# Connector_0.net
KiCad netlist of a schematic drawn in Altium Designer
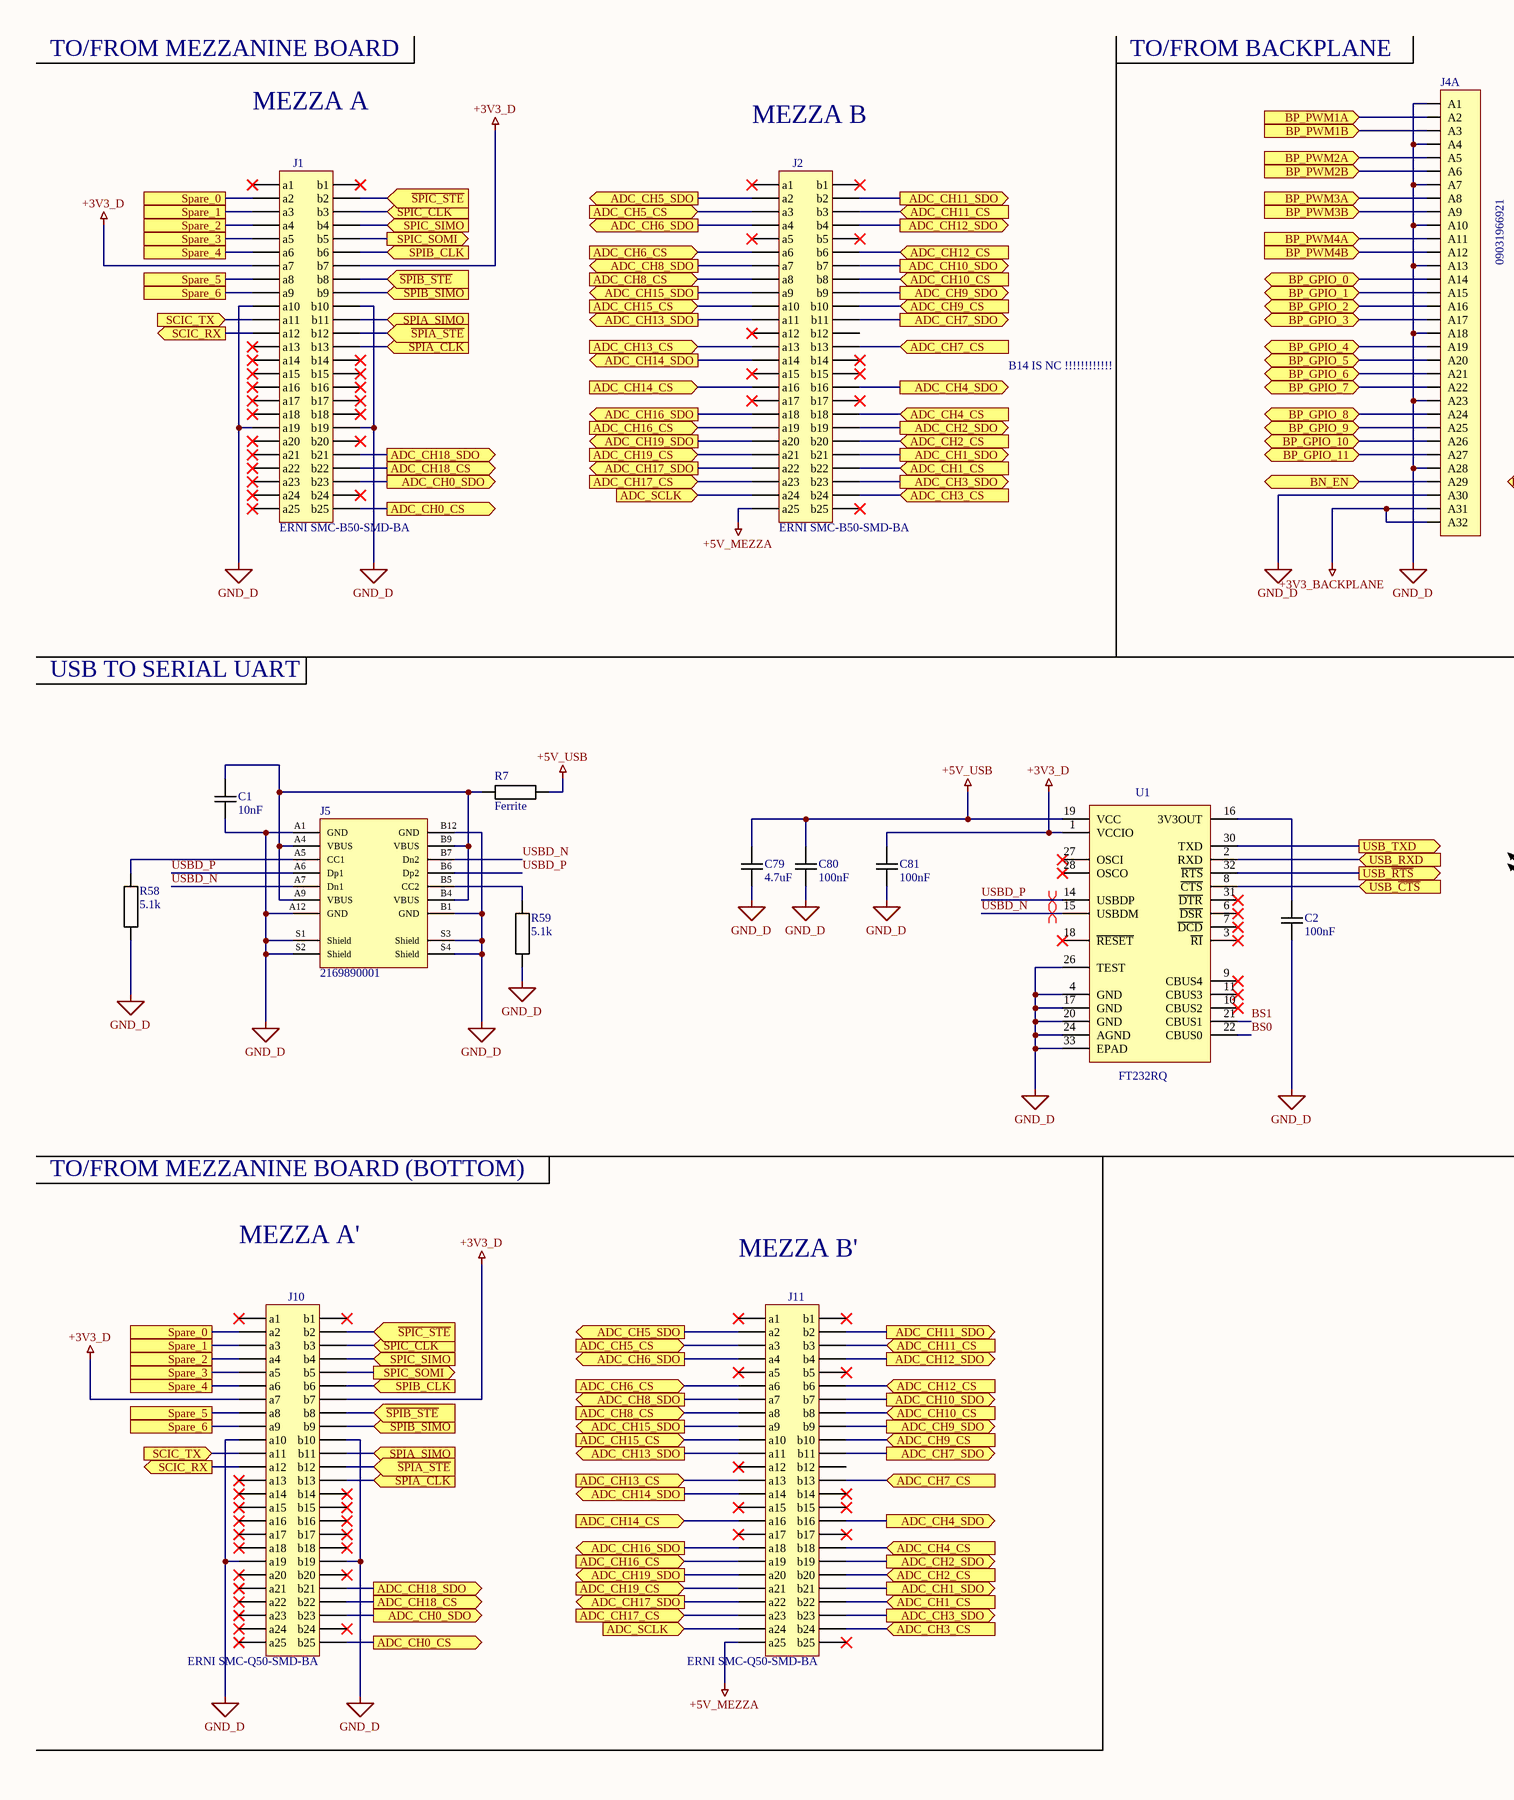
[diagram p0: Connector_0.SchDoc, left]
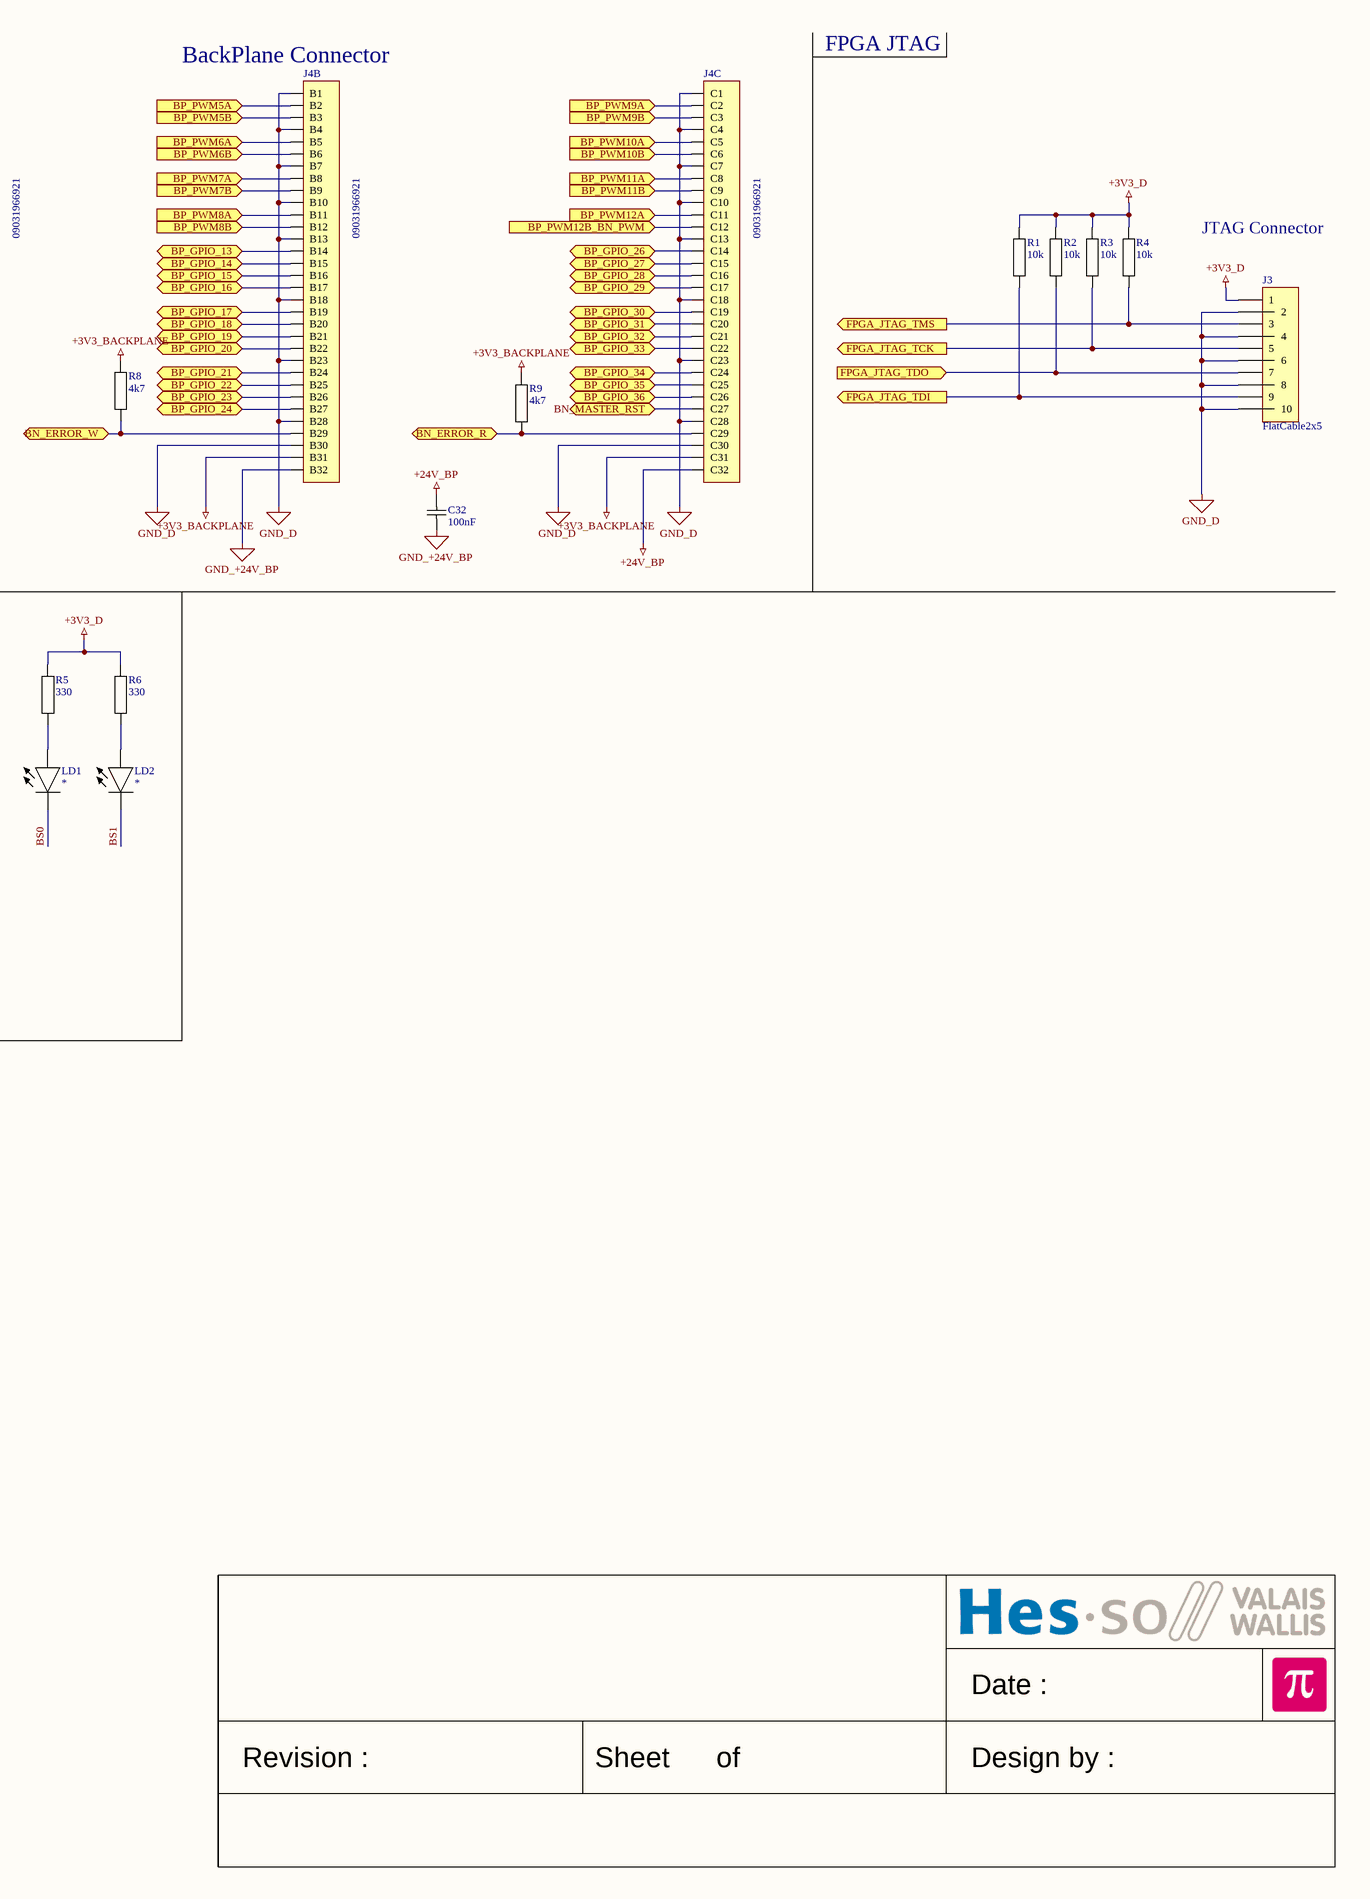
[diagram p1: Connector_0.SchDoc, right]

(export (version "E")
  (design (tool "Eeschema 10.0.6"))
  (components
    (comp (ref "C1")
      (value "10nF")
      (footprint "CAPACITOR 1608 REFLOW")
      (description "Capacitor X7R 10% 50V 1608(0603)")
      (libsource (lib "Capacitor") (part "Capacitor"))
    )
    (comp (ref "C2")
      (value "100nF")
      (footprint "CAPACITOR 1608 REFLOW")
      (description "Capacitor X7R 10% 50V 1608(0603)")
      (libsource (lib "Capacitor") (part "Capacitor"))
    )
    (comp (ref "C32")
      (value "100nF")
      (footprint "CAPACITOR 1608 REFLOW")
      (description "Capacitor X7R 10% 50V 1608(0603)")
      (libsource (lib "Capacitor") (part "Capacitor"))
    )
    (comp (ref "C79")
      (value "4.7uF")
      (footprint "CAPACITOR 1608 REFLOW")
      (description "Capacitor X7R 10% 50V 1608(0603)")
      (libsource (lib "Capacitor") (part "Capacitor"))
    )
    (comp (ref "C80")
      (value "100nF")
      (footprint "CAPACITOR 1608 REFLOW")
      (description "Capacitor X7R 10% 50V 1608(0603)")
      (libsource (lib "Capacitor") (part "Capacitor"))
    )
    (comp (ref "C81")
      (value "100nF")
      (footprint "CAPACITOR 1608 REFLOW")
      (description "Capacitor X7R 10% 50V 1608(0603)")
      (libsource (lib "Capacitor") (part "Capacitor"))
    )
    (comp (ref "J1")
      (value "ERNI SMC-B50-SMD-BA")
      (footprint "ERNI SMC-B50-SMD-BA")
      (description "Female 1.27 pitch 2x25 pin connector")
      (libsource (lib "Connector") (part "ERNI SMC-B50-SMD-BA"))
    )
    (comp (ref "J2")
      (value "ERNI SMC-B50-SMD-BA")
      (footprint "ERNI SMC-B50-SMD-BA")
      (description "Female 1.27 pitch 2x25 pin connector")
      (libsource (lib "Connector") (part "ERNI SMC-B50-SMD-BA"))
    )
    (comp (ref "J3")
      (value "FlatCable2x5")
      (footprint "FlatCable2x5 2MM Right Angle TH FCI 98614-G61-10ULF")
      (libsource (lib "Connector") (part "FlatCable2x5"))
    )
    (comp (ref "J4")
      (value "09031966921")
      (footprint "DIN41612 MALE 3X32 ABC R90")
      (description "DIN41612 MALE 3X32 ABC R90")
      (fields (field (name "MANUFACTURER") "Harting"))
      (libsource (lib "Connector") (part "DIN41612 MALE 3X32 ABC R90"))
    )
    (comp (ref "J5")
      (value "2169890001")
      (footprint "USB-C-TH MOLEX 2169890001")
      (description "USB-C Receptacle Connector 24 Position Through Hole, Right Angle")
      (libsource (lib "Connector") (part "USB-C-Molex 2169890001"))
    )
    (comp (ref "J10")
      (value "ERNI SMC-Q50-SMD-BA")
      (footprint "ERNI SMC-Q50-SMD-BA")
      (description "Male 1.27 pitch 2x25 pin connector")
      (libsource (lib "Connector") (part "ERNI SMC-Q50-SMD-BA"))
    )
    (comp (ref "J11")
      (value "ERNI SMC-Q50-SMD-BA")
      (footprint "ERNI SMC-Q50-SMD-BA")
      (description "Male 1.27 pitch 2x25 pin connector")
      (libsource (lib "Connector") (part "ERNI SMC-Q50-SMD-BA"))
    )
    (comp (ref "LD1")
      (value "*")
      (footprint "LED 1608 REFLOW")
      (description "LED generic")
      (libsource (lib "Diode") (part "LED"))
    )
    (comp (ref "LD2")
      (value "*")
      (footprint "LED 1608 REFLOW")
      (description "LED generic")
      (libsource (lib "Diode") (part "LED"))
    )
    (comp (ref "R1")
      (value "10k")
      (footprint "RESISTOR 1608 REFLOW")
      (description "Resistor 1% 50V 100mW 1608(0603)")
      (libsource (lib "Resistor") (part "Resistor"))
    )
    (comp (ref "R2")
      (value "10k")
      (footprint "RESISTOR 1608 REFLOW")
      (description "Resistor 1% 50V 100mW 1608(0603)")
      (libsource (lib "Resistor") (part "Resistor"))
    )
    (comp (ref "R3")
      (value "10k")
      (footprint "RESISTOR 1608 REFLOW")
      (description "Resistor 1% 50V 100mW 1608(0603)")
      (libsource (lib "Resistor") (part "Resistor"))
    )
    (comp (ref "R4")
      (value "10k")
      (footprint "RESISTOR 1608 REFLOW")
      (description "Resistor 1% 50V 100mW 1608(0603)")
      (libsource (lib "Resistor") (part "Resistor"))
    )
    (comp (ref "R5")
      (value "330")
      (footprint "RESISTOR 1608 REFLOW")
      (description "Resistor 1% 50V 125mW 2012(0805)")
      (libsource (lib "Resistor") (part "Resistor"))
    )
    (comp (ref "R6")
      (value "330")
      (footprint "RESISTOR 1608 REFLOW")
      (description "Resistor 1% 50V 125mW 2012(0805)")
      (libsource (lib "Resistor") (part "Resistor"))
    )
    (comp (ref "R7")
      (value "Ferrite")
      (footprint "RESISTOR 1608 REFLOW")
      (description "Resistor 1% 50V 100mW 1608(0603)")
      (libsource (lib "Resistor") (part "Resistor"))
    )
    (comp (ref "R8")
      (value "4k7")
      (footprint "RESISTOR 1608 REFLOW")
      (description "Resistor 1% 50V 100mW 1608(0603)")
      (libsource (lib "Resistor") (part "Resistor"))
    )
    (comp (ref "R9")
      (value "4k7")
      (footprint "RESISTOR 1608 REFLOW")
      (description "Resistor 1% 50V 100mW 1608(0603)")
      (libsource (lib "Resistor") (part "Resistor"))
    )
    (comp (ref "R58")
      (value "5.1k")
      (footprint "RESISTOR 1608 REFLOW")
      (description "Resistor 1% 50V 100mW 1608(0603)")
      (libsource (lib "Resistor") (part "Resistor"))
    )
    (comp (ref "R59")
      (value "5.1k")
      (footprint "RESISTOR 1608 REFLOW")
      (description "Resistor 1% 50V 100mW 1608(0603)")
      (libsource (lib "Resistor") (part "Resistor"))
    )
    (comp (ref "U1")
      (value "FT232RQ")
      (footprint "QFN32 P0.5 T3.2x3.2 C5.0X5.0 H1.0")
      (description "24-Bit ADC with Ultra Low Noise PGIA - Crystal")
      (libsource (lib "IntegratedCircuit - Copy") (part "FT232RQ"))
    )
  )
  (nets
    (net (code "1") (name "+3V3_BACKPLANE") (class "Default")
      (node (ref "J4") (pin "A31") (pinfunction "A31_A31") (pintype "passive"))
      (node (ref "J4") (pin "A32") (pinfunction "A32_A32") (pintype "passive"))
      (node (ref "J4") (pin "B31") (pinfunction "B31_B31") (pintype "passive"))
      (node (ref "J4") (pin "C31") (pinfunction "C31_C31") (pintype "passive"))
      (node (ref "R8") (pin "2") (pinfunction "2_2") (pintype "passive"))
      (node (ref "R9") (pin "2") (pinfunction "2_2") (pintype "passive"))
    )
    (net (code "2") (name "+3V3_D") (class "Default")
      (node (ref "C81") (pin "2") (pinfunction "2_2") (pintype "passive"))
      (node (ref "J1") (pin "a7") (pinfunction "a7_a7") (pintype "passive"))
      (node (ref "J1") (pin "b7") (pinfunction "b7_b7") (pintype "passive"))
      (node (ref "J10") (pin "a7") (pinfunction "a7_a7") (pintype "passive"))
      (node (ref "J10") (pin "b7") (pinfunction "b7_b7") (pintype "passive"))
      (node (ref "J3") (pin "1") (pinfunction "1_1") (pintype "passive"))
      (node (ref "R1") (pin "2") (pinfunction "2_2") (pintype "passive"))
      (node (ref "R2") (pin "2") (pinfunction "2_2") (pintype "passive"))
      (node (ref "R3") (pin "2") (pinfunction "2_2") (pintype "passive"))
      (node (ref "R4") (pin "2") (pinfunction "2_2") (pintype "passive"))
      (node (ref "R5") (pin "2") (pinfunction "2_2") (pintype "passive"))
      (node (ref "R6") (pin "2") (pinfunction "2_2") (pintype "passive"))
      (node (ref "U1") (pin "1") (pinfunction "VCCIO_1") (pintype "passive"))
    )
    (net (code "3") (name "+5V_MEZZA") (class "Default")
      (node (ref "J11") (pin "a25") (pinfunction "a25_a25") (pintype "passive"))
      (node (ref "J2") (pin "a25") (pinfunction "a25_a25") (pintype "passive"))
    )
    (net (code "4") (name "+5V_USB") (class "Default")
      (node (ref "C79") (pin "2") (pinfunction "2_2") (pintype "passive"))
      (node (ref "C80") (pin "2") (pinfunction "2_2") (pintype "passive"))
      (node (ref "R7") (pin "2") (pinfunction "2_2") (pintype "passive"))
      (node (ref "U1") (pin "19") (pinfunction "VCC_19") (pintype "passive"))
    )
    (net (code "5") (name "+24V_BP") (class "Default")
      (node (ref "C32") (pin "2") (pinfunction "2_2") (pintype "passive"))
      (node (ref "J4") (pin "C32") (pinfunction "C32_C32") (pintype "passive"))
    )
    (net (code "6") (name "/ADC_CH0_CS") (class "Default")
      (node (ref "J1") (pin "b25") (pinfunction "b25_b25") (pintype "passive"))
      (node (ref "J10") (pin "b25") (pinfunction "b25_b25") (pintype "passive"))
    )
    (net (code "7") (name "/ADC_CH0_SDO") (class "Default")
      (node (ref "J1") (pin "b23") (pinfunction "b23_b23") (pintype "passive"))
      (node (ref "J10") (pin "b23") (pinfunction "b23_b23") (pintype "passive"))
    )
    (net (code "8") (name "/ADC_CH1_CS") (class "Default")
      (node (ref "J11") (pin "b22") (pinfunction "b22_b22") (pintype "passive"))
      (node (ref "J2") (pin "b22") (pinfunction "b22_b22") (pintype "passive"))
    )
    (net (code "9") (name "/ADC_CH1_SDO") (class "Default")
      (node (ref "J11") (pin "b21") (pinfunction "b21_b21") (pintype "passive"))
      (node (ref "J2") (pin "b21") (pinfunction "b21_b21") (pintype "passive"))
    )
    (net (code "10") (name "/ADC_CH2_CS") (class "Default")
      (node (ref "J11") (pin "b20") (pinfunction "b20_b20") (pintype "passive"))
      (node (ref "J2") (pin "b20") (pinfunction "b20_b20") (pintype "passive"))
    )
    (net (code "11") (name "/ADC_CH2_SDO") (class "Default")
      (node (ref "J11") (pin "b19") (pinfunction "b19_b19") (pintype "passive"))
      (node (ref "J2") (pin "b19") (pinfunction "b19_b19") (pintype "passive"))
    )
    (net (code "12") (name "/ADC_CH3_CS") (class "Default")
      (node (ref "J11") (pin "b24") (pinfunction "b24_b24") (pintype "passive"))
      (node (ref "J2") (pin "b24") (pinfunction "b24_b24") (pintype "passive"))
    )
    (net (code "13") (name "/ADC_CH3_SDO") (class "Default")
      (node (ref "J11") (pin "b23") (pinfunction "b23_b23") (pintype "passive"))
      (node (ref "J2") (pin "b23") (pinfunction "b23_b23") (pintype "passive"))
    )
    (net (code "14") (name "/ADC_CH4_CS") (class "Default")
      (node (ref "J11") (pin "b18") (pinfunction "b18_b18") (pintype "passive"))
      (node (ref "J2") (pin "b18") (pinfunction "b18_b18") (pintype "passive"))
    )
    (net (code "15") (name "/ADC_CH4_SDO") (class "Default")
      (node (ref "J11") (pin "b16") (pinfunction "b16_b16") (pintype "passive"))
      (node (ref "J2") (pin "b16") (pinfunction "b16_b16") (pintype "passive"))
    )
    (net (code "16") (name "/ADC_CH5_CS") (class "Default")
      (node (ref "J11") (pin "a3") (pinfunction "a3_a3") (pintype "passive"))
      (node (ref "J2") (pin "a3") (pinfunction "a3_a3") (pintype "passive"))
    )
    (net (code "17") (name "/ADC_CH5_SDO") (class "Default")
      (node (ref "J11") (pin "a2") (pinfunction "a2_a2") (pintype "passive"))
      (node (ref "J2") (pin "a2") (pinfunction "a2_a2") (pintype "passive"))
    )
    (net (code "18") (name "/ADC_CH6_CS") (class "Default")
      (node (ref "J11") (pin "a6") (pinfunction "a6_a6") (pintype "passive"))
      (node (ref "J2") (pin "a6") (pinfunction "a6_a6") (pintype "passive"))
    )
    (net (code "19") (name "/ADC_CH6_SDO") (class "Default")
      (node (ref "J11") (pin "a4") (pinfunction "a4_a4") (pintype "passive"))
      (node (ref "J2") (pin "a4") (pinfunction "a4_a4") (pintype "passive"))
    )
    (net (code "20") (name "/ADC_CH7_CS") (class "Default")
      (node (ref "J11") (pin "b13") (pinfunction "b13_b13") (pintype "passive"))
      (node (ref "J2") (pin "b13") (pinfunction "b13_b13") (pintype "passive"))
    )
    (net (code "21") (name "/ADC_CH7_SDO") (class "Default")
      (node (ref "J11") (pin "b11") (pinfunction "b11_b11") (pintype "passive"))
      (node (ref "J2") (pin "b11") (pinfunction "b11_b11") (pintype "passive"))
    )
    (net (code "22") (name "/ADC_CH8_CS") (class "Default")
      (node (ref "J11") (pin "a8") (pinfunction "a8_a8") (pintype "passive"))
      (node (ref "J2") (pin "a8") (pinfunction "a8_a8") (pintype "passive"))
    )
    (net (code "23") (name "/ADC_CH8_SDO") (class "Default")
      (node (ref "J11") (pin "a7") (pinfunction "a7_a7") (pintype "passive"))
      (node (ref "J2") (pin "a7") (pinfunction "a7_a7") (pintype "passive"))
    )
    (net (code "24") (name "/ADC_CH9_CS") (class "Default")
      (node (ref "J11") (pin "b10") (pinfunction "b10_b10") (pintype "passive"))
      (node (ref "J2") (pin "b10") (pinfunction "b10_b10") (pintype "passive"))
    )
    (net (code "25") (name "/ADC_CH9_SDO") (class "Default")
      (node (ref "J11") (pin "b9") (pinfunction "b9_b9") (pintype "passive"))
      (node (ref "J2") (pin "b9") (pinfunction "b9_b9") (pintype "passive"))
    )
    (net (code "26") (name "/ADC_CH10_CS") (class "Default")
      (node (ref "J11") (pin "b8") (pinfunction "b8_b8") (pintype "passive"))
      (node (ref "J2") (pin "b8") (pinfunction "b8_b8") (pintype "passive"))
    )
    (net (code "27") (name "/ADC_CH10_SDO") (class "Default")
      (node (ref "J11") (pin "b7") (pinfunction "b7_b7") (pintype "passive"))
      (node (ref "J2") (pin "b7") (pinfunction "b7_b7") (pintype "passive"))
    )
    (net (code "28") (name "/ADC_CH11_CS") (class "Default")
      (node (ref "J11") (pin "b3") (pinfunction "b3_b3") (pintype "passive"))
      (node (ref "J2") (pin "b3") (pinfunction "b3_b3") (pintype "passive"))
    )
    (net (code "29") (name "/ADC_CH11_SDO") (class "Default")
      (node (ref "J11") (pin "b2") (pinfunction "b2_b2") (pintype "passive"))
      (node (ref "J2") (pin "b2") (pinfunction "b2_b2") (pintype "passive"))
    )
    (net (code "30") (name "/ADC_CH12_CS") (class "Default")
      (node (ref "J11") (pin "b6") (pinfunction "b6_b6") (pintype "passive"))
      (node (ref "J2") (pin "b6") (pinfunction "b6_b6") (pintype "passive"))
    )
    (net (code "31") (name "/ADC_CH12_SDO") (class "Default")
      (node (ref "J11") (pin "b4") (pinfunction "b4_b4") (pintype "passive"))
      (node (ref "J2") (pin "b4") (pinfunction "b4_b4") (pintype "passive"))
    )
    (net (code "32") (name "/ADC_CH13_CS") (class "Default")
      (node (ref "J11") (pin "a13") (pinfunction "a13_a13") (pintype "passive"))
      (node (ref "J2") (pin "a13") (pinfunction "a13_a13") (pintype "passive"))
    )
    (net (code "33") (name "/ADC_CH13_SDO") (class "Default")
      (node (ref "J11") (pin "a11") (pinfunction "a11_a11") (pintype "passive"))
      (node (ref "J2") (pin "a11") (pinfunction "a11_a11") (pintype "passive"))
    )
    (net (code "34") (name "/ADC_CH14_CS") (class "Default")
      (node (ref "J11") (pin "a16") (pinfunction "a16_a16") (pintype "passive"))
      (node (ref "J2") (pin "a16") (pinfunction "a16_a16") (pintype "passive"))
    )
    (net (code "35") (name "/ADC_CH14_SDO") (class "Default")
      (node (ref "J11") (pin "a14") (pinfunction "a14_a14") (pintype "passive"))
      (node (ref "J2") (pin "a14") (pinfunction "a14_a14") (pintype "passive"))
    )
    (net (code "36") (name "/ADC_CH15_CS") (class "Default")
      (node (ref "J11") (pin "a10") (pinfunction "a10_a10") (pintype "passive"))
      (node (ref "J2") (pin "a10") (pinfunction "a10_a10") (pintype "passive"))
    )
    (net (code "37") (name "/ADC_CH15_SDO") (class "Default")
      (node (ref "J11") (pin "a9") (pinfunction "a9_a9") (pintype "passive"))
      (node (ref "J2") (pin "a9") (pinfunction "a9_a9") (pintype "passive"))
    )
    (net (code "38") (name "/ADC_CH16_CS") (class "Default")
      (node (ref "J11") (pin "a19") (pinfunction "a19_a19") (pintype "passive"))
      (node (ref "J2") (pin "a19") (pinfunction "a19_a19") (pintype "passive"))
    )
    (net (code "39") (name "/ADC_CH16_SDO") (class "Default")
      (node (ref "J11") (pin "a18") (pinfunction "a18_a18") (pintype "passive"))
      (node (ref "J2") (pin "a18") (pinfunction "a18_a18") (pintype "passive"))
    )
    (net (code "40") (name "/ADC_CH17_CS") (class "Default")
      (node (ref "J11") (pin "a23") (pinfunction "a23_a23") (pintype "passive"))
      (node (ref "J2") (pin "a23") (pinfunction "a23_a23") (pintype "passive"))
    )
    (net (code "41") (name "/ADC_CH17_SDO") (class "Default")
      (node (ref "J11") (pin "a22") (pinfunction "a22_a22") (pintype "passive"))
      (node (ref "J2") (pin "a22") (pinfunction "a22_a22") (pintype "passive"))
    )
    (net (code "42") (name "/ADC_CH18_CS") (class "Default")
      (node (ref "J1") (pin "b22") (pinfunction "b22_b22") (pintype "passive"))
      (node (ref "J10") (pin "b22") (pinfunction "b22_b22") (pintype "passive"))
    )
    (net (code "43") (name "/ADC_CH18_SDO") (class "Default")
      (node (ref "J1") (pin "b21") (pinfunction "b21_b21") (pintype "passive"))
      (node (ref "J10") (pin "b21") (pinfunction "b21_b21") (pintype "passive"))
    )
    (net (code "44") (name "/ADC_CH19_CS") (class "Default")
      (node (ref "J11") (pin "a21") (pinfunction "a21_a21") (pintype "passive"))
      (node (ref "J2") (pin "a21") (pinfunction "a21_a21") (pintype "passive"))
    )
    (net (code "45") (name "/ADC_CH19_SDO") (class "Default")
      (node (ref "J11") (pin "a20") (pinfunction "a20_a20") (pintype "passive"))
      (node (ref "J2") (pin "a20") (pinfunction "a20_a20") (pintype "passive"))
    )
    (net (code "46") (name "/ADC_SCLK") (class "Default")
      (node (ref "J11") (pin "a24") (pinfunction "a24_a24") (pintype "passive"))
      (node (ref "J2") (pin "a24") (pinfunction "a24_a24") (pintype "passive"))
    )
    (net (code "47") (name "/BN_EN") (class "Default")
      (node (ref "J4") (pin "A29") (pinfunction "A29_A29") (pintype "passive"))
    )
    (net (code "48") (name "/BN_ERROR_R") (class "Default")
      (node (ref "J4") (pin "C29") (pinfunction "C29_C29") (pintype "passive"))
      (node (ref "R9") (pin "1") (pinfunction "1_1") (pintype "passive"))
    )
    (net (code "49") (name "/BN_ERROR_W") (class "Default")
      (node (ref "J4") (pin "B29") (pinfunction "B29_B29") (pintype "passive"))
      (node (ref "R8") (pin "1") (pinfunction "1_1") (pintype "passive"))
    )
    (net (code "50") (name "/BN_MASTER_RST") (class "Default")
      (node (ref "J4") (pin "C27") (pinfunction "C27_C27") (pintype "passive"))
    )
    (net (code "51") (name "/BP_GPIO_0") (class "Default")
      (node (ref "J4") (pin "A14") (pinfunction "A14_A14") (pintype "passive"))
    )
    (net (code "52") (name "/BP_GPIO_1") (class "Default")
      (node (ref "J4") (pin "A15") (pinfunction "A15_A15") (pintype "passive"))
    )
    (net (code "53") (name "/BP_GPIO_2") (class "Default")
      (node (ref "J4") (pin "A16") (pinfunction "A16_A16") (pintype "passive"))
    )
    (net (code "54") (name "/BP_GPIO_3") (class "Default")
      (node (ref "J4") (pin "A17") (pinfunction "A17_A17") (pintype "passive"))
    )
    (net (code "55") (name "/BP_GPIO_4") (class "Default")
      (node (ref "J4") (pin "A19") (pinfunction "A19_A19") (pintype "passive"))
    )
    (net (code "56") (name "/BP_GPIO_5") (class "Default")
      (node (ref "J4") (pin "A20") (pinfunction "A20_A20") (pintype "passive"))
    )
    (net (code "57") (name "/BP_GPIO_6") (class "Default")
      (node (ref "J4") (pin "A21") (pinfunction "A21_A21") (pintype "passive"))
    )
    (net (code "58") (name "/BP_GPIO_7") (class "Default")
      (node (ref "J4") (pin "A22") (pinfunction "A22_A22") (pintype "passive"))
    )
    (net (code "59") (name "/BP_GPIO_8") (class "Default")
      (node (ref "J4") (pin "A24") (pinfunction "A24_A24") (pintype "passive"))
    )
    (net (code "60") (name "/BP_GPIO_9") (class "Default")
      (node (ref "J4") (pin "A25") (pinfunction "A25_A25") (pintype "passive"))
    )
    (net (code "61") (name "/BP_GPIO_10") (class "Default")
      (node (ref "J4") (pin "A26") (pinfunction "A26_A26") (pintype "passive"))
    )
    (net (code "62") (name "/BP_GPIO_11") (class "Default")
      (node (ref "J4") (pin "A27") (pinfunction "A27_A27") (pintype "passive"))
    )
    (net (code "63") (name "/BP_GPIO_13") (class "Default")
      (node (ref "J4") (pin "B14") (pinfunction "B14_B14") (pintype "passive"))
    )
    (net (code "64") (name "/BP_GPIO_14") (class "Default")
      (node (ref "J4") (pin "B15") (pinfunction "B15_B15") (pintype "passive"))
    )
    (net (code "65") (name "/BP_GPIO_15") (class "Default")
      (node (ref "J4") (pin "B16") (pinfunction "B16_B16") (pintype "passive"))
    )
    (net (code "66") (name "/BP_GPIO_16") (class "Default")
      (node (ref "J4") (pin "B17") (pinfunction "B17_B17") (pintype "passive"))
    )
    (net (code "67") (name "/BP_GPIO_17") (class "Default")
      (node (ref "J4") (pin "B19") (pinfunction "B19_B19") (pintype "passive"))
    )
    (net (code "68") (name "/BP_GPIO_18") (class "Default")
      (node (ref "J4") (pin "B20") (pinfunction "B20_B20") (pintype "passive"))
    )
    (net (code "69") (name "/BP_GPIO_19") (class "Default")
      (node (ref "J4") (pin "B21") (pinfunction "B21_B21") (pintype "passive"))
    )
    (net (code "70") (name "/BP_GPIO_20") (class "Default")
      (node (ref "J4") (pin "B22") (pinfunction "B22_B22") (pintype "passive"))
    )
    (net (code "71") (name "/BP_GPIO_21") (class "Default")
      (node (ref "J4") (pin "B24") (pinfunction "B24_B24") (pintype "passive"))
    )
    (net (code "72") (name "/BP_GPIO_22") (class "Default")
      (node (ref "J4") (pin "B25") (pinfunction "B25_B25") (pintype "passive"))
    )
    (net (code "73") (name "/BP_GPIO_23") (class "Default")
      (node (ref "J4") (pin "B26") (pinfunction "B26_B26") (pintype "passive"))
    )
    (net (code "74") (name "/BP_GPIO_24") (class "Default")
      (node (ref "J4") (pin "B27") (pinfunction "B27_B27") (pintype "passive"))
    )
    (net (code "75") (name "/BP_GPIO_26") (class "Default")
      (node (ref "J4") (pin "C14") (pinfunction "C14_C14") (pintype "passive"))
    )
    (net (code "76") (name "/BP_GPIO_27") (class "Default")
      (node (ref "J4") (pin "C15") (pinfunction "C15_C15") (pintype "passive"))
    )
    (net (code "77") (name "/BP_GPIO_28") (class "Default")
      (node (ref "J4") (pin "C16") (pinfunction "C16_C16") (pintype "passive"))
    )
    (net (code "78") (name "/BP_GPIO_29") (class "Default")
      (node (ref "J4") (pin "C17") (pinfunction "C17_C17") (pintype "passive"))
    )
    (net (code "79") (name "/BP_GPIO_30") (class "Default")
      (node (ref "J4") (pin "C19") (pinfunction "C19_C19") (pintype "passive"))
    )
    (net (code "80") (name "/BP_GPIO_31") (class "Default")
      (node (ref "J4") (pin "C20") (pinfunction "C20_C20") (pintype "passive"))
    )
    (net (code "81") (name "/BP_GPIO_32") (class "Default")
      (node (ref "J4") (pin "C21") (pinfunction "C21_C21") (pintype "passive"))
    )
    (net (code "82") (name "/BP_GPIO_33") (class "Default")
      (node (ref "J4") (pin "C22") (pinfunction "C22_C22") (pintype "passive"))
    )
    (net (code "83") (name "/BP_GPIO_34") (class "Default")
      (node (ref "J4") (pin "C24") (pinfunction "C24_C24") (pintype "passive"))
    )
    (net (code "84") (name "/BP_GPIO_35") (class "Default")
      (node (ref "J4") (pin "C25") (pinfunction "C25_C25") (pintype "passive"))
    )
    (net (code "85") (name "/BP_GPIO_36") (class "Default")
      (node (ref "J4") (pin "C26") (pinfunction "C26_C26") (pintype "passive"))
    )
    (net (code "86") (name "/BP_PWM1A") (class "Default")
      (node (ref "J4") (pin "A2") (pinfunction "A2_A2") (pintype "passive"))
    )
    (net (code "87") (name "/BP_PWM1B") (class "Default")
      (node (ref "J4") (pin "A3") (pinfunction "A3_A3") (pintype "passive"))
    )
    (net (code "88") (name "/BP_PWM2A") (class "Default")
      (node (ref "J4") (pin "A5") (pinfunction "A5_A5") (pintype "passive"))
    )
    (net (code "89") (name "/BP_PWM2B") (class "Default")
      (node (ref "J4") (pin "A6") (pinfunction "A6_A6") (pintype "passive"))
    )
    (net (code "90") (name "/BP_PWM3A") (class "Default")
      (node (ref "J4") (pin "A8") (pinfunction "A8_A8") (pintype "passive"))
    )
    (net (code "91") (name "/BP_PWM3B") (class "Default")
      (node (ref "J4") (pin "A9") (pinfunction "A9_A9") (pintype "passive"))
    )
    (net (code "92") (name "/BP_PWM4A") (class "Default")
      (node (ref "J4") (pin "A11") (pinfunction "A11_A11") (pintype "passive"))
    )
    (net (code "93") (name "/BP_PWM4B") (class "Default")
      (node (ref "J4") (pin "A12") (pinfunction "A12_A12") (pintype "passive"))
    )
    (net (code "94") (name "/BP_PWM5A") (class "Default")
      (node (ref "J4") (pin "B2") (pinfunction "B2_B2") (pintype "passive"))
    )
    (net (code "95") (name "/BP_PWM5B") (class "Default")
      (node (ref "J4") (pin "B3") (pinfunction "B3_B3") (pintype "passive"))
    )
    (net (code "96") (name "/BP_PWM6A") (class "Default")
      (node (ref "J4") (pin "B5") (pinfunction "B5_B5") (pintype "passive"))
    )
    (net (code "97") (name "/BP_PWM6B") (class "Default")
      (node (ref "J4") (pin "B6") (pinfunction "B6_B6") (pintype "passive"))
    )
    (net (code "98") (name "/BP_PWM7A") (class "Default")
      (node (ref "J4") (pin "B8") (pinfunction "B8_B8") (pintype "passive"))
    )
    (net (code "99") (name "/BP_PWM7B") (class "Default")
      (node (ref "J4") (pin "B9") (pinfunction "B9_B9") (pintype "passive"))
    )
    (net (code "100") (name "/BP_PWM8A") (class "Default")
      (node (ref "J4") (pin "B11") (pinfunction "B11_B11") (pintype "passive"))
    )
    (net (code "101") (name "/BP_PWM8B") (class "Default")
      (node (ref "J4") (pin "B12") (pinfunction "B12_B12") (pintype "passive"))
    )
    (net (code "102") (name "/BP_PWM9A") (class "Default")
      (node (ref "J4") (pin "C2") (pinfunction "C2_C2") (pintype "passive"))
    )
    (net (code "103") (name "/BP_PWM9B") (class "Default")
      (node (ref "J4") (pin "C3") (pinfunction "C3_C3") (pintype "passive"))
    )
    (net (code "104") (name "/BP_PWM10A") (class "Default")
      (node (ref "J4") (pin "C5") (pinfunction "C5_C5") (pintype "passive"))
    )
    (net (code "105") (name "/BP_PWM10B") (class "Default")
      (node (ref "J4") (pin "C6") (pinfunction "C6_C6") (pintype "passive"))
    )
    (net (code "106") (name "/BP_PWM11A") (class "Default")
      (node (ref "J4") (pin "C8") (pinfunction "C8_C8") (pintype "passive"))
    )
    (net (code "107") (name "/BP_PWM11B") (class "Default")
      (node (ref "J4") (pin "C9") (pinfunction "C9_C9") (pintype "passive"))
    )
    (net (code "108") (name "/BP_PWM12A") (class "Default")
      (node (ref "J4") (pin "C11") (pinfunction "C11_C11") (pintype "passive"))
    )
    (net (code "109") (name "/BP_PWM12B_BN_PWM") (class "Default")
      (node (ref "J4") (pin "C12") (pinfunction "C12_C12") (pintype "passive"))
    )
    (net (code "110") (name "/BS0") (class "Default")
      (node (ref "LD1") (pin "1") (pinfunction "C_1") (pintype "passive"))
      (node (ref "U1") (pin "22") (pinfunction "CBUS0_22") (pintype "passive"))
    )
    (net (code "111") (name "/BS1") (class "Default")
      (node (ref "LD2") (pin "1") (pinfunction "C_1") (pintype "passive"))
      (node (ref "U1") (pin "21") (pinfunction "CBUS1_21") (pintype "passive"))
    )
    (net (code "112") (name "/FPGA_JTAG_TCK") (class "Default")
      (node (ref "J3") (pin "5") (pinfunction "5_5") (pintype "passive"))
      (node (ref "R3") (pin "1") (pinfunction "1_1") (pintype "passive"))
    )
    (net (code "113") (name "/FPGA_JTAG_TDI") (class "Default")
      (node (ref "J3") (pin "9") (pinfunction "9_9") (pintype "passive"))
      (node (ref "R1") (pin "1") (pinfunction "1_1") (pintype "passive"))
    )
    (net (code "114") (name "/FPGA_JTAG_TDO") (class "Default")
      (node (ref "J3") (pin "7") (pinfunction "7_7") (pintype "passive"))
      (node (ref "R2") (pin "1") (pinfunction "1_1") (pintype "passive"))
    )
    (net (code "115") (name "/FPGA_JTAG_TMS") (class "Default")
      (node (ref "J3") (pin "3") (pinfunction "3_3") (pintype "passive"))
      (node (ref "R4") (pin "1") (pinfunction "1_1") (pintype "passive"))
    )
    (net (code "116") (name "/SCIC_RX") (class "Default")
      (node (ref "J1") (pin "a12") (pinfunction "a12_a12") (pintype "passive"))
      (node (ref "J10") (pin "a12") (pinfunction "a12_a12") (pintype "passive"))
    )
    (net (code "117") (name "/SCIC_TX") (class "Default")
      (node (ref "J1") (pin "a11") (pinfunction "a11_a11") (pintype "passive"))
      (node (ref "J10") (pin "a11") (pinfunction "a11_a11") (pintype "passive"))
    )
    (net (code "118") (name "/SPIA_CLK") (class "Default")
      (node (ref "J1") (pin "b13") (pinfunction "b13_b13") (pintype "passive"))
      (node (ref "J10") (pin "b13") (pinfunction "b13_b13") (pintype "passive"))
    )
    (net (code "119") (name "/SPIA_SIMO") (class "Default")
      (node (ref "J1") (pin "b11") (pinfunction "b11_b11") (pintype "passive"))
      (node (ref "J10") (pin "b11") (pinfunction "b11_b11") (pintype "passive"))
    )
    (net (code "120") (name "/SPIB_CLK") (class "Default")
      (node (ref "J1") (pin "b6") (pinfunction "b6_b6") (pintype "passive"))
      (node (ref "J10") (pin "b6") (pinfunction "b6_b6") (pintype "passive"))
    )
    (net (code "121") (name "/SPIB_SIMO") (class "Default")
      (node (ref "J1") (pin "b9") (pinfunction "b9_b9") (pintype "passive"))
      (node (ref "J10") (pin "b9") (pinfunction "b9_b9") (pintype "passive"))
    )
    (net (code "122") (name "/SPIC_CLK") (class "Default")
      (node (ref "J1") (pin "b3") (pinfunction "b3_b3") (pintype "passive"))
      (node (ref "J10") (pin "b3") (pinfunction "b3_b3") (pintype "passive"))
    )
    (net (code "123") (name "/SPIC_SIMO") (class "Default")
      (node (ref "J1") (pin "b4") (pinfunction "b4_b4") (pintype "passive"))
      (node (ref "J10") (pin "b4") (pinfunction "b4_b4") (pintype "passive"))
    )
    (net (code "124") (name "/SPIC_SOMI") (class "Default")
      (node (ref "J1") (pin "b5") (pinfunction "b5_b5") (pintype "passive"))
      (node (ref "J10") (pin "b5") (pinfunction "b5_b5") (pintype "passive"))
    )
    (net (code "125") (name "/Spare_0") (class "Default")
      (node (ref "J1") (pin "a2") (pinfunction "a2_a2") (pintype "passive"))
      (node (ref "J10") (pin "a2") (pinfunction "a2_a2") (pintype "passive"))
    )
    (net (code "126") (name "/Spare_1") (class "Default")
      (node (ref "J1") (pin "a3") (pinfunction "a3_a3") (pintype "passive"))
      (node (ref "J10") (pin "a3") (pinfunction "a3_a3") (pintype "passive"))
    )
    (net (code "127") (name "/Spare_2") (class "Default")
      (node (ref "J1") (pin "a4") (pinfunction "a4_a4") (pintype "passive"))
      (node (ref "J10") (pin "a4") (pinfunction "a4_a4") (pintype "passive"))
    )
    (net (code "128") (name "/Spare_3") (class "Default")
      (node (ref "J1") (pin "a5") (pinfunction "a5_a5") (pintype "passive"))
      (node (ref "J10") (pin "a5") (pinfunction "a5_a5") (pintype "passive"))
    )
    (net (code "129") (name "/Spare_4") (class "Default")
      (node (ref "J1") (pin "a6") (pinfunction "a6_a6") (pintype "passive"))
      (node (ref "J10") (pin "a6") (pinfunction "a6_a6") (pintype "passive"))
    )
    (net (code "130") (name "/Spare_5") (class "Default")
      (node (ref "J1") (pin "a8") (pinfunction "a8_a8") (pintype "passive"))
      (node (ref "J10") (pin "a8") (pinfunction "a8_a8") (pintype "passive"))
    )
    (net (code "131") (name "/Spare_6") (class "Default")
      (node (ref "J1") (pin "a9") (pinfunction "a9_a9") (pintype "passive"))
      (node (ref "J10") (pin "a9") (pinfunction "a9_a9") (pintype "passive"))
    )
    (net (code "132") (name "/USBD_N") (class "Default")
      (node (ref "J5") (pin "A7") (pinfunction "Dn1_A7") (pintype "passive"))
      (node (ref "J5") (pin "B7") (pinfunction "Dn2_B7") (pintype "passive"))
      (node (ref "U1") (pin "15") (pinfunction "USBDM_15") (pintype "passive"))
    )
    (net (code "133") (name "/USBD_P") (class "Default")
      (node (ref "J5") (pin "A6") (pinfunction "Dp1_A6") (pintype "passive"))
      (node (ref "J5") (pin "B6") (pinfunction "Dp2_B6") (pintype "passive"))
      (node (ref "U1") (pin "14") (pinfunction "USBDP_14") (pintype "passive"))
    )
    (net (code "134") (name "/USB_RXD") (class "Default")
      (node (ref "U1") (pin "2") (pinfunction "RXD_2") (pintype "passive"))
    )
    (net (code "135") (name "/USB_TXD") (class "Default")
      (node (ref "U1") (pin "30") (pinfunction "TXD_30") (pintype "passive"))
    )
    (net (code "136") (name "/USB_~{CTS}") (class "Default")
      (node (ref "U1") (pin "8") (pinfunction "~{CTS}_8") (pintype "passive"))
    )
    (net (code "137") (name "/USB_~{RTS}") (class "Default")
      (node (ref "U1") (pin "32") (pinfunction "~{RTS}_32") (pintype "passive"))
    )
    (net (code "138") (name "/~{SPIA_STE}") (class "Default")
      (node (ref "J1") (pin "b12") (pinfunction "b12_b12") (pintype "passive"))
      (node (ref "J10") (pin "b12") (pinfunction "b12_b12") (pintype "passive"))
    )
    (net (code "139") (name "/~{SPIB_STE}") (class "Default")
      (node (ref "J1") (pin "b8") (pinfunction "b8_b8") (pintype "passive"))
      (node (ref "J10") (pin "b8") (pinfunction "b8_b8") (pintype "passive"))
    )
    (net (code "140") (name "/~{SPIC_STE}") (class "Default")
      (node (ref "J1") (pin "b2") (pinfunction "b2_b2") (pintype "passive"))
      (node (ref "J10") (pin "b2") (pinfunction "b2_b2") (pintype "passive"))
    )
    (net (code "141") (name "GND_+24V_BP") (class "Default")
      (node (ref "C32") (pin "1") (pinfunction "1_1") (pintype "passive"))
      (node (ref "J4") (pin "B32") (pinfunction "B32_B32") (pintype "passive"))
    )
    (net (code "142") (name "GND_D") (class "Default")
      (node (ref "C1") (pin "1") (pinfunction "1_1") (pintype "passive"))
      (node (ref "C2") (pin "1") (pinfunction "1_1") (pintype "passive"))
      (node (ref "C79") (pin "1") (pinfunction "1_1") (pintype "passive"))
      (node (ref "C80") (pin "1") (pinfunction "1_1") (pintype "passive"))
      (node (ref "C81") (pin "1") (pinfunction "1_1") (pintype "passive"))
      (node (ref "J1") (pin "a10") (pinfunction "a10_a10") (pintype "passive"))
      (node (ref "J1") (pin "a19") (pinfunction "a19_a19") (pintype "passive"))
      (node (ref "J1") (pin "b10") (pinfunction "b10_b10") (pintype "passive"))
      (node (ref "J1") (pin "b19") (pinfunction "b19_b19") (pintype "passive"))
      (node (ref "J10") (pin "a10") (pinfunction "a10_a10") (pintype "passive"))
      (node (ref "J10") (pin "a19") (pinfunction "a19_a19") (pintype "passive"))
      (node (ref "J10") (pin "b10") (pinfunction "b10_b10") (pintype "passive"))
      (node (ref "J10") (pin "b19") (pinfunction "b19_b19") (pintype "passive"))
      (node (ref "J3") (pin "10") (pinfunction "10_10") (pintype "passive"))
      (node (ref "J3") (pin "2") (pinfunction "2_2") (pintype "passive"))
      (node (ref "J3") (pin "4") (pinfunction "4_4") (pintype "passive"))
      (node (ref "J3") (pin "6") (pinfunction "6_6") (pintype "passive"))
      (node (ref "J3") (pin "8") (pinfunction "8_8") (pintype "passive"))
      (node (ref "J4") (pin "A1") (pinfunction "A1_A1") (pintype "passive"))
      (node (ref "J4") (pin "A10") (pinfunction "A10_A10") (pintype "passive"))
      (node (ref "J4") (pin "A13") (pinfunction "A13_A13") (pintype "passive"))
      (node (ref "J4") (pin "A18") (pinfunction "A18_A18") (pintype "passive"))
      (node (ref "J4") (pin "A23") (pinfunction "A23_A23") (pintype "passive"))
      (node (ref "J4") (pin "A28") (pinfunction "A28_A28") (pintype "passive"))
      (node (ref "J4") (pin "A30") (pinfunction "A30_A30") (pintype "passive"))
      (node (ref "J4") (pin "A4") (pinfunction "A4_A4") (pintype "passive"))
      (node (ref "J4") (pin "A7") (pinfunction "A7_A7") (pintype "passive"))
      (node (ref "J4") (pin "B1") (pinfunction "B1_B1") (pintype "passive"))
      (node (ref "J4") (pin "B10") (pinfunction "B10_B10") (pintype "passive"))
      (node (ref "J4") (pin "B13") (pinfunction "B13_B13") (pintype "passive"))
      (node (ref "J4") (pin "B18") (pinfunction "B18_B18") (pintype "passive"))
      (node (ref "J4") (pin "B23") (pinfunction "B23_B23") (pintype "passive"))
      (node (ref "J4") (pin "B28") (pinfunction "B28_B28") (pintype "passive"))
      (node (ref "J4") (pin "B30") (pinfunction "B30_B30") (pintype "passive"))
      (node (ref "J4") (pin "B4") (pinfunction "B4_B4") (pintype "passive"))
      (node (ref "J4") (pin "B7") (pinfunction "B7_B7") (pintype "passive"))
      (node (ref "J4") (pin "C1") (pinfunction "C1_C1") (pintype "passive"))
      (node (ref "J4") (pin "C10") (pinfunction "C10_C10") (pintype "passive"))
      (node (ref "J4") (pin "C13") (pinfunction "C13_C13") (pintype "passive"))
      (node (ref "J4") (pin "C18") (pinfunction "C18_C18") (pintype "passive"))
      (node (ref "J4") (pin "C23") (pinfunction "C23_C23") (pintype "passive"))
      (node (ref "J4") (pin "C28") (pinfunction "C28_C28") (pintype "passive"))
      (node (ref "J4") (pin "C30") (pinfunction "C30_C30") (pintype "passive"))
      (node (ref "J4") (pin "C4") (pinfunction "C4_C4") (pintype "passive"))
      (node (ref "J4") (pin "C7") (pinfunction "C7_C7") (pintype "passive"))
      (node (ref "J5") (pin "A1") (pinfunction "GND_A1") (pintype "passive"))
      (node (ref "J5") (pin "A12") (pinfunction "GND_A12") (pintype "passive"))
      (node (ref "J5") (pin "B1") (pinfunction "GND_B1") (pintype "passive"))
      (node (ref "J5") (pin "B12") (pinfunction "GND_B12") (pintype "passive"))
      (node (ref "J5") (pin "S1") (pinfunction "Shield_S1") (pintype "passive"))
      (node (ref "J5") (pin "S2") (pinfunction "Shield_S2") (pintype "passive"))
      (node (ref "J5") (pin "S3") (pinfunction "Shield_S3") (pintype "passive"))
      (node (ref "J5") (pin "S4") (pinfunction "Shield_S4") (pintype "passive"))
      (node (ref "R58") (pin "2") (pinfunction "2_2") (pintype "passive"))
      (node (ref "R59") (pin "2") (pinfunction "2_2") (pintype "passive"))
      (node (ref "U1") (pin "17") (pinfunction "GND_17") (pintype "passive"))
      (node (ref "U1") (pin "20") (pinfunction "GND_20") (pintype "passive"))
      (node (ref "U1") (pin "24") (pinfunction "AGND_24") (pintype "passive"))
      (node (ref "U1") (pin "26") (pinfunction "TEST_26") (pintype "passive"))
      (node (ref "U1") (pin "33") (pinfunction "EPAD_33") (pintype "passive"))
      (node (ref "U1") (pin "4") (pinfunction "GND_4") (pintype "passive"))
    )
    (net (code "143") (name "Net-(C1-Pad2)") (class "Default")
      (node (ref "C1") (pin "2") (pinfunction "2_2") (pintype "passive"))
      (node (ref "J5") (pin "A4") (pinfunction "VBUS_A4") (pintype "passive"))
      (node (ref "J5") (pin "A9") (pinfunction "VBUS_A9") (pintype "passive"))
      (node (ref "J5") (pin "B4") (pinfunction "VBUS_B4") (pintype "passive"))
      (node (ref "J5") (pin "B9") (pinfunction "VBUS_B9") (pintype "passive"))
      (node (ref "R7") (pin "1") (pinfunction "1_1") (pintype "passive"))
    )
    (net (code "144") (name "Net-(J5-CC1)") (class "Default")
      (node (ref "J5") (pin "A5") (pinfunction "CC1_A5") (pintype "passive"))
      (node (ref "R58") (pin "1") (pinfunction "1_1") (pintype "passive"))
    )
    (net (code "145") (name "Net-(J5-CC2)") (class "Default")
      (node (ref "J5") (pin "B5") (pinfunction "CC2_B5") (pintype "passive"))
      (node (ref "R59") (pin "1") (pinfunction "1_1") (pintype "passive"))
    )
    (net (code "146") (name "Net-(LD1-A)") (class "Default")
      (node (ref "LD1") (pin "2") (pinfunction "A_2") (pintype "passive"))
      (node (ref "R5") (pin "1") (pinfunction "1_1") (pintype "passive"))
    )
    (net (code "147") (name "Net-(LD2-A)") (class "Default")
      (node (ref "LD2") (pin "2") (pinfunction "A_2") (pintype "passive"))
      (node (ref "R6") (pin "1") (pinfunction "1_1") (pintype "passive"))
    )
    (net (code "148") (name "Net-(U1-3V3OUT)") (class "Default")
      (node (ref "C2") (pin "2") (pinfunction "2_2") (pintype "passive"))
      (node (ref "U1") (pin "16") (pinfunction "3V3OUT_16") (pintype "passive"))
    )
    (net (code "149") (name "unconnected-(J1-Pada1)") (class "Default")
      (node (ref "J1") (pin "a1") (pinfunction "a1_a1") (pintype "passive+no_connect"))
    )
    (net (code "150") (name "unconnected-(J1-Pada13)") (class "Default")
      (node (ref "J1") (pin "a13") (pinfunction "a13_a13") (pintype "passive+no_connect"))
    )
    (net (code "151") (name "unconnected-(J1-Pada14)") (class "Default")
      (node (ref "J1") (pin "a14") (pinfunction "a14_a14") (pintype "passive+no_connect"))
    )
    (net (code "152") (name "unconnected-(J1-Pada15)") (class "Default")
      (node (ref "J1") (pin "a15") (pinfunction "a15_a15") (pintype "passive+no_connect"))
    )
    (net (code "153") (name "unconnected-(J1-Pada16)") (class "Default")
      (node (ref "J1") (pin "a16") (pinfunction "a16_a16") (pintype "passive+no_connect"))
    )
    (net (code "154") (name "unconnected-(J1-Pada17)") (class "Default")
      (node (ref "J1") (pin "a17") (pinfunction "a17_a17") (pintype "passive+no_connect"))
    )
    (net (code "155") (name "unconnected-(J1-Pada18)") (class "Default")
      (node (ref "J1") (pin "a18") (pinfunction "a18_a18") (pintype "passive+no_connect"))
    )
    (net (code "156") (name "unconnected-(J1-Pada20)") (class "Default")
      (node (ref "J1") (pin "a20") (pinfunction "a20_a20") (pintype "passive+no_connect"))
    )
    (net (code "157") (name "unconnected-(J1-Pada21)") (class "Default")
      (node (ref "J1") (pin "a21") (pinfunction "a21_a21") (pintype "passive+no_connect"))
    )
    (net (code "158") (name "unconnected-(J1-Pada22)") (class "Default")
      (node (ref "J1") (pin "a22") (pinfunction "a22_a22") (pintype "passive+no_connect"))
    )
    (net (code "159") (name "unconnected-(J1-Pada23)") (class "Default")
      (node (ref "J1") (pin "a23") (pinfunction "a23_a23") (pintype "passive+no_connect"))
    )
    (net (code "160") (name "unconnected-(J1-Pada24)") (class "Default")
      (node (ref "J1") (pin "a24") (pinfunction "a24_a24") (pintype "passive+no_connect"))
    )
    (net (code "161") (name "unconnected-(J1-Pada25)") (class "Default")
      (node (ref "J1") (pin "a25") (pinfunction "a25_a25") (pintype "passive+no_connect"))
    )
    (net (code "162") (name "unconnected-(J1-Padb1)") (class "Default")
      (node (ref "J1") (pin "b1") (pinfunction "b1_b1") (pintype "passive+no_connect"))
    )
    (net (code "163") (name "unconnected-(J1-Padb14)") (class "Default")
      (node (ref "J1") (pin "b14") (pinfunction "b14_b14") (pintype "passive+no_connect"))
    )
    (net (code "164") (name "unconnected-(J1-Padb15)") (class "Default")
      (node (ref "J1") (pin "b15") (pinfunction "b15_b15") (pintype "passive+no_connect"))
    )
    (net (code "165") (name "unconnected-(J1-Padb16)") (class "Default")
      (node (ref "J1") (pin "b16") (pinfunction "b16_b16") (pintype "passive+no_connect"))
    )
    (net (code "166") (name "unconnected-(J1-Padb17)") (class "Default")
      (node (ref "J1") (pin "b17") (pinfunction "b17_b17") (pintype "passive+no_connect"))
    )
    (net (code "167") (name "unconnected-(J1-Padb18)") (class "Default")
      (node (ref "J1") (pin "b18") (pinfunction "b18_b18") (pintype "passive+no_connect"))
    )
    (net (code "168") (name "unconnected-(J1-Padb20)") (class "Default")
      (node (ref "J1") (pin "b20") (pinfunction "b20_b20") (pintype "passive+no_connect"))
    )
    (net (code "169") (name "unconnected-(J1-Padb24)") (class "Default")
      (node (ref "J1") (pin "b24") (pinfunction "b24_b24") (pintype "passive+no_connect"))
    )
    (net (code "170") (name "unconnected-(J2-Pada1)") (class "Default")
      (node (ref "J2") (pin "a1") (pinfunction "a1_a1") (pintype "passive+no_connect"))
    )
    (net (code "171") (name "unconnected-(J2-Pada5)") (class "Default")
      (node (ref "J2") (pin "a5") (pinfunction "a5_a5") (pintype "passive+no_connect"))
    )
    (net (code "172") (name "unconnected-(J2-Pada12)") (class "Default")
      (node (ref "J2") (pin "a12") (pinfunction "a12_a12") (pintype "passive+no_connect"))
    )
    (net (code "173") (name "unconnected-(J2-Pada15)") (class "Default")
      (node (ref "J2") (pin "a15") (pinfunction "a15_a15") (pintype "passive+no_connect"))
    )
    (net (code "174") (name "unconnected-(J2-Pada17)") (class "Default")
      (node (ref "J2") (pin "a17") (pinfunction "a17_a17") (pintype "passive+no_connect"))
    )
    (net (code "175") (name "unconnected-(J2-Padb1)") (class "Default")
      (node (ref "J2") (pin "b1") (pinfunction "b1_b1") (pintype "passive+no_connect"))
    )
    (net (code "176") (name "unconnected-(J2-Padb5)") (class "Default")
      (node (ref "J2") (pin "b5") (pinfunction "b5_b5") (pintype "passive+no_connect"))
    )
    (net (code "177") (name "unconnected-(J2-Padb12)") (class "Default")
      (node (ref "J2") (pin "b12") (pinfunction "b12_b12") (pintype "passive"))
    )
    (net (code "178") (name "unconnected-(J2-Padb14)") (class "Default")
      (node (ref "J2") (pin "b14") (pinfunction "b14_b14") (pintype "passive+no_connect"))
    )
    (net (code "179") (name "unconnected-(J2-Padb15)") (class "Default")
      (node (ref "J2") (pin "b15") (pinfunction "b15_b15") (pintype "passive+no_connect"))
    )
    (net (code "180") (name "unconnected-(J2-Padb17)") (class "Default")
      (node (ref "J2") (pin "b17") (pinfunction "b17_b17") (pintype "passive+no_connect"))
    )
    (net (code "181") (name "unconnected-(J2-Padb25)") (class "Default")
      (node (ref "J2") (pin "b25") (pinfunction "b25_b25") (pintype "passive+no_connect"))
    )
    (net (code "182") (name "unconnected-(J10-Pada1)") (class "Default")
      (node (ref "J10") (pin "a1") (pinfunction "a1_a1") (pintype "passive+no_connect"))
    )
    (net (code "183") (name "unconnected-(J10-Pada13)") (class "Default")
      (node (ref "J10") (pin "a13") (pinfunction "a13_a13") (pintype "passive+no_connect"))
    )
    (net (code "184") (name "unconnected-(J10-Pada14)") (class "Default")
      (node (ref "J10") (pin "a14") (pinfunction "a14_a14") (pintype "passive+no_connect"))
    )
    (net (code "185") (name "unconnected-(J10-Pada15)") (class "Default")
      (node (ref "J10") (pin "a15") (pinfunction "a15_a15") (pintype "passive+no_connect"))
    )
    (net (code "186") (name "unconnected-(J10-Pada16)") (class "Default")
      (node (ref "J10") (pin "a16") (pinfunction "a16_a16") (pintype "passive+no_connect"))
    )
    (net (code "187") (name "unconnected-(J10-Pada17)") (class "Default")
      (node (ref "J10") (pin "a17") (pinfunction "a17_a17") (pintype "passive+no_connect"))
    )
    (net (code "188") (name "unconnected-(J10-Pada18)") (class "Default")
      (node (ref "J10") (pin "a18") (pinfunction "a18_a18") (pintype "passive+no_connect"))
    )
    (net (code "189") (name "unconnected-(J10-Pada20)") (class "Default")
      (node (ref "J10") (pin "a20") (pinfunction "a20_a20") (pintype "passive+no_connect"))
    )
    (net (code "190") (name "unconnected-(J10-Pada21)") (class "Default")
      (node (ref "J10") (pin "a21") (pinfunction "a21_a21") (pintype "passive+no_connect"))
    )
    (net (code "191") (name "unconnected-(J10-Pada22)") (class "Default")
      (node (ref "J10") (pin "a22") (pinfunction "a22_a22") (pintype "passive+no_connect"))
    )
    (net (code "192") (name "unconnected-(J10-Pada23)") (class "Default")
      (node (ref "J10") (pin "a23") (pinfunction "a23_a23") (pintype "passive+no_connect"))
    )
    (net (code "193") (name "unconnected-(J10-Pada24)") (class "Default")
      (node (ref "J10") (pin "a24") (pinfunction "a24_a24") (pintype "passive+no_connect"))
    )
    (net (code "194") (name "unconnected-(J10-Pada25)") (class "Default")
      (node (ref "J10") (pin "a25") (pinfunction "a25_a25") (pintype "passive+no_connect"))
    )
    (net (code "195") (name "unconnected-(J10-Padb1)") (class "Default")
      (node (ref "J10") (pin "b1") (pinfunction "b1_b1") (pintype "passive+no_connect"))
    )
    (net (code "196") (name "unconnected-(J10-Padb14)") (class "Default")
      (node (ref "J10") (pin "b14") (pinfunction "b14_b14") (pintype "passive+no_connect"))
    )
    (net (code "197") (name "unconnected-(J10-Padb15)") (class "Default")
      (node (ref "J10") (pin "b15") (pinfunction "b15_b15") (pintype "passive+no_connect"))
    )
    (net (code "198") (name "unconnected-(J10-Padb16)") (class "Default")
      (node (ref "J10") (pin "b16") (pinfunction "b16_b16") (pintype "passive+no_connect"))
    )
    (net (code "199") (name "unconnected-(J10-Padb17)") (class "Default")
      (node (ref "J10") (pin "b17") (pinfunction "b17_b17") (pintype "passive+no_connect"))
    )
    (net (code "200") (name "unconnected-(J10-Padb18)") (class "Default")
      (node (ref "J10") (pin "b18") (pinfunction "b18_b18") (pintype "passive+no_connect"))
    )
    (net (code "201") (name "unconnected-(J10-Padb20)") (class "Default")
      (node (ref "J10") (pin "b20") (pinfunction "b20_b20") (pintype "passive+no_connect"))
    )
    (net (code "202") (name "unconnected-(J10-Padb24)") (class "Default")
      (node (ref "J10") (pin "b24") (pinfunction "b24_b24") (pintype "passive+no_connect"))
    )
    (net (code "203") (name "unconnected-(J11-Pada1)") (class "Default")
      (node (ref "J11") (pin "a1") (pinfunction "a1_a1") (pintype "passive+no_connect"))
    )
    (net (code "204") (name "unconnected-(J11-Pada5)") (class "Default")
      (node (ref "J11") (pin "a5") (pinfunction "a5_a5") (pintype "passive+no_connect"))
    )
    (net (code "205") (name "unconnected-(J11-Pada12)") (class "Default")
      (node (ref "J11") (pin "a12") (pinfunction "a12_a12") (pintype "passive+no_connect"))
    )
    (net (code "206") (name "unconnected-(J11-Pada15)") (class "Default")
      (node (ref "J11") (pin "a15") (pinfunction "a15_a15") (pintype "passive+no_connect"))
    )
    (net (code "207") (name "unconnected-(J11-Pada17)") (class "Default")
      (node (ref "J11") (pin "a17") (pinfunction "a17_a17") (pintype "passive+no_connect"))
    )
    (net (code "208") (name "unconnected-(J11-Padb1)") (class "Default")
      (node (ref "J11") (pin "b1") (pinfunction "b1_b1") (pintype "passive+no_connect"))
    )
    (net (code "209") (name "unconnected-(J11-Padb5)") (class "Default")
      (node (ref "J11") (pin "b5") (pinfunction "b5_b5") (pintype "passive+no_connect"))
    )
    (net (code "210") (name "unconnected-(J11-Padb12)") (class "Default")
      (node (ref "J11") (pin "b12") (pinfunction "b12_b12") (pintype "passive"))
    )
    (net (code "211") (name "unconnected-(J11-Padb14)") (class "Default")
      (node (ref "J11") (pin "b14") (pinfunction "b14_b14") (pintype "passive+no_connect"))
    )
    (net (code "212") (name "unconnected-(J11-Padb15)") (class "Default")
      (node (ref "J11") (pin "b15") (pinfunction "b15_b15") (pintype "passive+no_connect"))
    )
    (net (code "213") (name "unconnected-(J11-Padb17)") (class "Default")
      (node (ref "J11") (pin "b17") (pinfunction "b17_b17") (pintype "passive+no_connect"))
    )
    (net (code "214") (name "unconnected-(J11-Padb25)") (class "Default")
      (node (ref "J11") (pin "b25") (pinfunction "b25_b25") (pintype "passive+no_connect"))
    )
    (net (code "215") (name "unconnected-(U1-CBUS2-Pad10)") (class "Default")
      (node (ref "U1") (pin "10") (pinfunction "CBUS2_10") (pintype "passive+no_connect"))
    )
    (net (code "216") (name "unconnected-(U1-CBUS3-Pad11)") (class "Default")
      (node (ref "U1") (pin "11") (pinfunction "CBUS3_11") (pintype "passive+no_connect"))
    )
    (net (code "217") (name "unconnected-(U1-CBUS4-Pad9)") (class "Default")
      (node (ref "U1") (pin "9") (pinfunction "CBUS4_9") (pintype "passive+no_connect"))
    )
    (net (code "218") (name "unconnected-(U1-OSCI-Pad27)") (class "Default")
      (node (ref "U1") (pin "27") (pinfunction "OSCI_27") (pintype "passive+no_connect"))
    )
    (net (code "219") (name "unconnected-(U1-OSCO-Pad28)") (class "Default")
      (node (ref "U1") (pin "28") (pinfunction "OSCO_28") (pintype "passive+no_connect"))
    )
    (net (code "220") (name "unconnected-(U1-Pad5)") (class "Default")
      (node (ref "U1") (pin "5") (pintype "passive"))
    )
    (net (code "221") (name "unconnected-(U1-Pad12)") (class "Default")
      (node (ref "U1") (pin "12") (pintype "passive"))
    )
    (net (code "222") (name "unconnected-(U1-Pad13)") (class "Default")
      (node (ref "U1") (pin "13") (pintype "passive"))
    )
    (net (code "223") (name "unconnected-(U1-Pad23)") (class "Default")
      (node (ref "U1") (pin "23") (pintype "passive"))
    )
    (net (code "224") (name "unconnected-(U1-Pad25)") (class "Default")
      (node (ref "U1") (pin "25") (pintype "passive"))
    )
    (net (code "225") (name "unconnected-(U1-Pad29)") (class "Default")
      (node (ref "U1") (pin "29") (pintype "passive"))
    )
    (net (code "226") (name "unconnected-(U1-~{DCD}-Pad7)") (class "Default")
      (node (ref "U1") (pin "7") (pinfunction "~{DCD}_7") (pintype "passive+no_connect"))
    )
    (net (code "227") (name "unconnected-(U1-~{DSR}-Pad6)") (class "Default")
      (node (ref "U1") (pin "6") (pinfunction "~{DSR}_6") (pintype "passive+no_connect"))
    )
    (net (code "228") (name "unconnected-(U1-~{DTR}-Pad31)") (class "Default")
      (node (ref "U1") (pin "31") (pinfunction "~{DTR}_31") (pintype "passive+no_connect"))
    )
    (net (code "229") (name "unconnected-(U1-~{RESET}-Pad18)") (class "Default")
      (node (ref "U1") (pin "18") (pinfunction "~{RESET}_18") (pintype "passive+no_connect"))
    )
    (net (code "230") (name "unconnected-(U1-~{RI}-Pad3)") (class "Default")
      (node (ref "U1") (pin "3") (pinfunction "~{RI}_3") (pintype "passive+no_connect"))
    )
  )
)
